# tic_tac_toe_wire.net
KiCad netlist of a schematic drawn in EAGLE
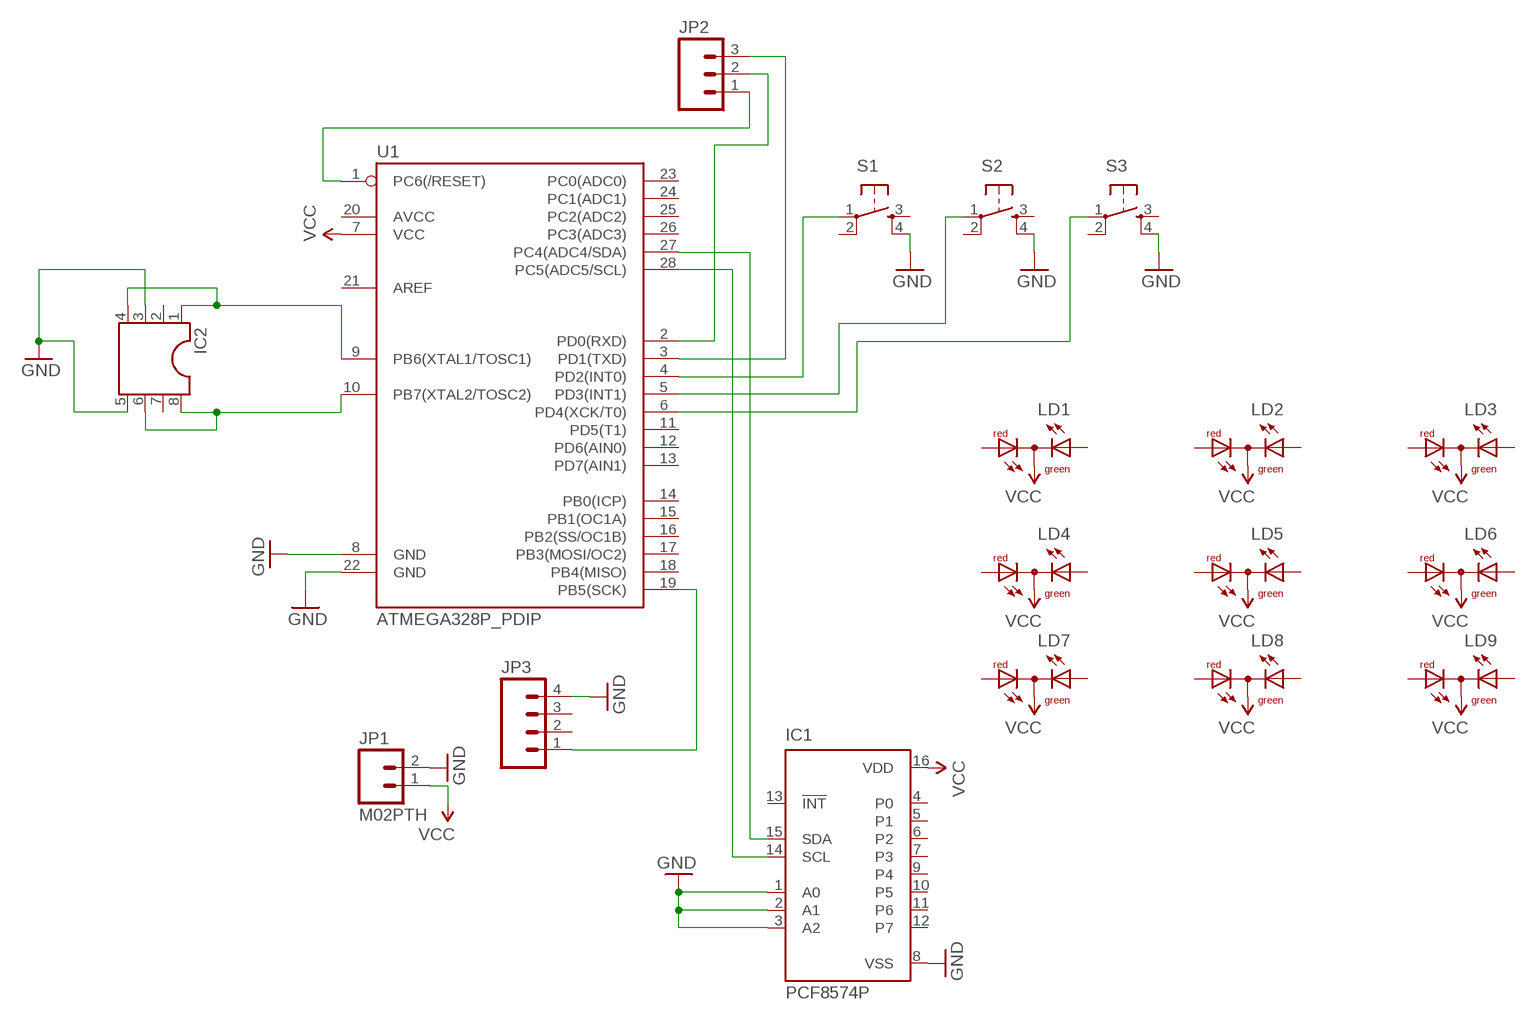
[diagram p0: schematic, sheet 1]

(export (version "E")
  (design (tool "Eeschema 10.0.6"))
  (components
    (comp (ref "IC1")
      (value "PCF8574P")
      (footprint "eagle-import:DIL16")
      (fields (field (name "MPN") "PCF8574PN"))
      (libsource (lib "eagle-import") (part "PCF8574P"))
    )
    (comp (ref "IC2")
      (value "DIL8S")
      (footprint "eagle-import:SOCKET-08")
      (libsource (lib "eagle-import") (part "DIL8S"))
    )
    (comp (ref "JP1")
      (value "M02PTH")
      (footprint "eagle-import:1X02")
      (libsource (lib "eagle-import") (part "M02PTH"))
    )
    (comp (ref "JP2")
      (value "M03PTH")
      (footprint "eagle-import:1X03")
      (libsource (lib "eagle-import") (part "M03PTH"))
    )
    (comp (ref "JP3")
      (value "M04PTH")
      (footprint "eagle-import:1X04")
      (libsource (lib "eagle-import") (part "M04PTH"))
    )
    (comp (ref "LD1")
      (value "DUOLED-RG-C")
      (footprint "eagle-import:DUOLED-C-5MM")
      (libsource (lib "eagle-import") (part "DUOLED-RG-C"))
    )
    (comp (ref "LD2")
      (value "DUOLED-RG-C")
      (footprint "eagle-import:DUOLED-C-5MM")
      (libsource (lib "eagle-import") (part "DUOLED-RG-C"))
    )
    (comp (ref "LD3")
      (value "DUOLED-RG-C")
      (footprint "eagle-import:DUOLED-C-5MM")
      (libsource (lib "eagle-import") (part "DUOLED-RG-C"))
    )
    (comp (ref "LD4")
      (value "DUOLED-RG-C")
      (footprint "eagle-import:DUOLED-C-5MM")
      (libsource (lib "eagle-import") (part "DUOLED-RG-C"))
    )
    (comp (ref "LD5")
      (value "DUOLED-RG-C")
      (footprint "eagle-import:DUOLED-C-5MM")
      (libsource (lib "eagle-import") (part "DUOLED-RG-C"))
    )
    (comp (ref "LD6")
      (value "DUOLED-RG-C")
      (footprint "eagle-import:DUOLED-C-5MM")
      (libsource (lib "eagle-import") (part "DUOLED-RG-C"))
    )
    (comp (ref "LD7")
      (value "DUOLED-RG-C")
      (footprint "eagle-import:DUOLED-C-5MM")
      (libsource (lib "eagle-import") (part "DUOLED-RG-C"))
    )
    (comp (ref "LD8")
      (value "DUOLED-RG-C")
      (footprint "eagle-import:DUOLED-C-5MM")
      (libsource (lib "eagle-import") (part "DUOLED-RG-C"))
    )
    (comp (ref "LD9")
      (value "DUOLED-RG-C")
      (footprint "eagle-import:DUOLED-C-5MM")
      (libsource (lib "eagle-import") (part "DUOLED-RG-C"))
    )
    (comp (ref "S1")
      (value "TAC_SWITCHPTH")
      (footprint "eagle-import:TACTILE-PTH")
      (libsource (lib "eagle-import") (part "TAC_SWITCHPTH"))
    )
    (comp (ref "S2")
      (value "TAC_SWITCHPTH")
      (footprint "eagle-import:TACTILE-PTH")
      (libsource (lib "eagle-import") (part "TAC_SWITCHPTH"))
    )
    (comp (ref "S3")
      (value "TAC_SWITCHPTH")
      (footprint "eagle-import:TACTILE-PTH")
      (libsource (lib "eagle-import") (part "TAC_SWITCHPTH"))
    )
    (comp (ref "U1")
      (value "ATMEGA328P_PDIP")
      (footprint "eagle-import:DIL28-3")
      (libsource (lib "eagle-import") (part "ATMEGA328P_PDIP"))
    )
  )
  (nets
    (net (code "1") (name "GND") (class "Default")
      (node (ref "IC1") (pin "1") (pinfunction "A0_1") (pintype "input"))
      (node (ref "IC1") (pin "2") (pinfunction "A1_2") (pintype "input"))
      (node (ref "IC1") (pin "3") (pinfunction "A2_3") (pintype "input"))
      (node (ref "IC1") (pin "8") (pinfunction "VSS_8") (pintype "power_in"))
      (node (ref "IC2") (pin "3") (pinfunction "3_3") (pintype "passive"))
      (node (ref "IC2") (pin "5") (pinfunction "5_5") (pintype "passive"))
      (node (ref "JP1") (pin "2") (pinfunction "2_2") (pintype "passive"))
      (node (ref "JP3") (pin "4") (pinfunction "4_4") (pintype "passive"))
      (node (ref "S1") (pin "4") (pinfunction "4_4") (pintype "passive"))
      (node (ref "S2") (pin "4") (pinfunction "4_4") (pintype "passive"))
      (node (ref "S3") (pin "4") (pinfunction "4_4") (pintype "passive"))
      (node (ref "U1") (pin "22") (pinfunction "GND_22") (pintype "bidirectional"))
      (node (ref "U1") (pin "8") (pinfunction "GND_8") (pintype "bidirectional"))
    )
    (net (code "2") (name "Net-(IC1-SCL)") (class "Default")
      (node (ref "IC1") (pin "14") (pinfunction "SCL_14") (pintype "input"))
      (node (ref "U1") (pin "28") (pinfunction "PC5(ADC5/SCL)_28") (pintype "bidirectional"))
    )
    (net (code "3") (name "Net-(IC1-SDA)") (class "Default")
      (node (ref "IC1") (pin "15") (pinfunction "SDA_15") (pintype "bidirectional"))
      (node (ref "U1") (pin "27") (pinfunction "PC4(ADC4/SDA)_27") (pintype "bidirectional"))
    )
    (net (code "4") (name "Net-(U1-PB5(SCK))") (class "Default")
      (node (ref "JP3") (pin "1") (pinfunction "1_1") (pintype "passive"))
      (node (ref "U1") (pin "19") (pinfunction "PB5(SCK)_19") (pintype "bidirectional"))
    )
    (net (code "5") (name "Net-(U1-PB6(XTAL1{slash}TOSC1))") (class "Default")
      (node (ref "IC2") (pin "1") (pinfunction "1_1") (pintype "passive"))
      (node (ref "IC2") (pin "4") (pinfunction "4_4") (pintype "passive"))
      (node (ref "U1") (pin "9") (pinfunction "PB6(XTAL1/TOSC1)_9") (pintype "bidirectional"))
    )
    (net (code "6") (name "Net-(U1-PB7(XTAL2{slash}TOSC2))") (class "Default")
      (node (ref "IC2") (pin "6") (pinfunction "6_6") (pintype "passive"))
      (node (ref "IC2") (pin "8") (pinfunction "8_8") (pintype "passive"))
      (node (ref "U1") (pin "10") (pinfunction "PB7(XTAL2/TOSC2)_10") (pintype "bidirectional"))
    )
    (net (code "7") (name "Net-(U1-PC6({slash}RESET))") (class "Default")
      (node (ref "JP2") (pin "1") (pinfunction "1_1") (pintype "passive"))
      (node (ref "U1") (pin "1") (pinfunction "PC6(/RESET)_1") (pintype "bidirectional"))
    )
    (net (code "8") (name "Net-(U1-PD0(RXD))") (class "Default")
      (node (ref "JP2") (pin "2") (pinfunction "2_2") (pintype "passive"))
      (node (ref "U1") (pin "2") (pinfunction "PD0(RXD)_2") (pintype "bidirectional"))
    )
    (net (code "9") (name "Net-(U1-PD1(TXD))") (class "Default")
      (node (ref "JP2") (pin "3") (pinfunction "3_3") (pintype "passive"))
      (node (ref "U1") (pin "3") (pinfunction "PD1(TXD)_3") (pintype "bidirectional"))
    )
    (net (code "10") (name "Net-(U1-PD2(INT0))") (class "Default")
      (node (ref "S1") (pin "1") (pinfunction "1_1") (pintype "passive"))
      (node (ref "U1") (pin "4") (pinfunction "PD2(INT0)_4") (pintype "bidirectional"))
    )
    (net (code "11") (name "Net-(U1-PD3(INT1))") (class "Default")
      (node (ref "S2") (pin "1") (pinfunction "1_1") (pintype "passive"))
      (node (ref "U1") (pin "5") (pinfunction "PD3(INT1)_5") (pintype "bidirectional"))
    )
    (net (code "12") (name "Net-(U1-PD4(XCK{slash}T0))") (class "Default")
      (node (ref "S3") (pin "1") (pinfunction "1_1") (pintype "passive"))
      (node (ref "U1") (pin "6") (pinfunction "PD4(XCK/T0)_6") (pintype "bidirectional"))
    )
    (net (code "13") (name "VCC") (class "Default")
      (node (ref "IC1") (pin "16") (pinfunction "VDD_16") (pintype "power_in"))
      (node (ref "JP1") (pin "1") (pinfunction "1_1") (pintype "passive"))
      (node (ref "LD1") (pin "C") (pinfunction "C_C") (pintype "passive"))
      (node (ref "LD2") (pin "C") (pinfunction "C_C") (pintype "passive"))
      (node (ref "LD3") (pin "C") (pinfunction "C_C") (pintype "passive"))
      (node (ref "LD4") (pin "C") (pinfunction "C_C") (pintype "passive"))
      (node (ref "LD5") (pin "C") (pinfunction "C_C") (pintype "passive"))
      (node (ref "LD6") (pin "C") (pinfunction "C_C") (pintype "passive"))
      (node (ref "LD7") (pin "C") (pinfunction "C_C") (pintype "passive"))
      (node (ref "LD8") (pin "C") (pinfunction "C_C") (pintype "passive"))
      (node (ref "LD9") (pin "C") (pinfunction "C_C") (pintype "passive"))
      (node (ref "U1") (pin "7") (pinfunction "VCC_7") (pintype "bidirectional"))
    )
    (net (code "14") (name "unconnected-(IC1-P0-Pad4)") (class "Default")
      (node (ref "IC1") (pin "4") (pinfunction "P0_4") (pintype "bidirectional"))
    )
    (net (code "15") (name "unconnected-(IC1-P1-Pad5)") (class "Default")
      (node (ref "IC1") (pin "5") (pinfunction "P1_5") (pintype "bidirectional"))
    )
    (net (code "16") (name "unconnected-(IC1-P2-Pad6)") (class "Default")
      (node (ref "IC1") (pin "6") (pinfunction "P2_6") (pintype "bidirectional"))
    )
    (net (code "17") (name "unconnected-(IC1-P3-Pad7)") (class "Default")
      (node (ref "IC1") (pin "7") (pinfunction "P3_7") (pintype "bidirectional"))
    )
    (net (code "18") (name "unconnected-(IC1-P4-Pad9)") (class "Default")
      (node (ref "IC1") (pin "9") (pinfunction "P4_9") (pintype "bidirectional"))
    )
    (net (code "19") (name "unconnected-(IC1-P5-Pad10)") (class "Default")
      (node (ref "IC1") (pin "10") (pinfunction "P5_10") (pintype "bidirectional"))
    )
    (net (code "20") (name "unconnected-(IC1-P6-Pad11)") (class "Default")
      (node (ref "IC1") (pin "11") (pinfunction "P6_11") (pintype "bidirectional"))
    )
    (net (code "21") (name "unconnected-(IC1-P7-Pad12)") (class "Default")
      (node (ref "IC1") (pin "12") (pinfunction "P7_12") (pintype "bidirectional"))
    )
    (net (code "22") (name "unconnected-(IC1-~{INT}-Pad13)") (class "Default")
      (node (ref "IC1") (pin "13") (pinfunction "~{INT}_13") (pintype "output"))
    )
    (net (code "23") (name "unconnected-(IC2-Pad2)") (class "Default")
      (node (ref "IC2") (pin "2") (pinfunction "2_2") (pintype "passive"))
    )
    (net (code "24") (name "unconnected-(IC2-Pad7)") (class "Default")
      (node (ref "IC2") (pin "7") (pinfunction "7_7") (pintype "passive"))
    )
    (net (code "25") (name "unconnected-(JP3-Pad2)") (class "Default")
      (node (ref "JP3") (pin "2") (pinfunction "2_2") (pintype "passive"))
    )
    (net (code "26") (name "unconnected-(JP3-Pad3)") (class "Default")
      (node (ref "JP3") (pin "3") (pinfunction "3_3") (pintype "passive"))
    )
    (net (code "27") (name "unconnected-(LD1-AG-PadAX)") (class "Default")
      (node (ref "LD1") (pin "AX") (pinfunction "AG_AX") (pintype "passive"))
    )
    (net (code "28") (name "unconnected-(LD1-PadAR)") (class "Default")
      (node (ref "LD1") (pin "AR") (pinfunction "AR_AR") (pintype "passive"))
    )
    (net (code "29") (name "unconnected-(LD2-AG-PadAX)") (class "Default")
      (node (ref "LD2") (pin "AX") (pinfunction "AG_AX") (pintype "passive"))
    )
    (net (code "30") (name "unconnected-(LD2-PadAR)") (class "Default")
      (node (ref "LD2") (pin "AR") (pinfunction "AR_AR") (pintype "passive"))
    )
    (net (code "31") (name "unconnected-(LD3-AG-PadAX)") (class "Default")
      (node (ref "LD3") (pin "AX") (pinfunction "AG_AX") (pintype "passive"))
    )
    (net (code "32") (name "unconnected-(LD3-PadAR)") (class "Default")
      (node (ref "LD3") (pin "AR") (pinfunction "AR_AR") (pintype "passive"))
    )
    (net (code "33") (name "unconnected-(LD4-AG-PadAX)") (class "Default")
      (node (ref "LD4") (pin "AX") (pinfunction "AG_AX") (pintype "passive"))
    )
    (net (code "34") (name "unconnected-(LD4-PadAR)") (class "Default")
      (node (ref "LD4") (pin "AR") (pinfunction "AR_AR") (pintype "passive"))
    )
    (net (code "35") (name "unconnected-(LD5-AG-PadAX)") (class "Default")
      (node (ref "LD5") (pin "AX") (pinfunction "AG_AX") (pintype "passive"))
    )
    (net (code "36") (name "unconnected-(LD5-PadAR)") (class "Default")
      (node (ref "LD5") (pin "AR") (pinfunction "AR_AR") (pintype "passive"))
    )
    (net (code "37") (name "unconnected-(LD6-AG-PadAX)") (class "Default")
      (node (ref "LD6") (pin "AX") (pinfunction "AG_AX") (pintype "passive"))
    )
    (net (code "38") (name "unconnected-(LD6-PadAR)") (class "Default")
      (node (ref "LD6") (pin "AR") (pinfunction "AR_AR") (pintype "passive"))
    )
    (net (code "39") (name "unconnected-(LD7-AG-PadAX)") (class "Default")
      (node (ref "LD7") (pin "AX") (pinfunction "AG_AX") (pintype "passive"))
    )
    (net (code "40") (name "unconnected-(LD7-PadAR)") (class "Default")
      (node (ref "LD7") (pin "AR") (pinfunction "AR_AR") (pintype "passive"))
    )
    (net (code "41") (name "unconnected-(LD8-AG-PadAX)") (class "Default")
      (node (ref "LD8") (pin "AX") (pinfunction "AG_AX") (pintype "passive"))
    )
    (net (code "42") (name "unconnected-(LD8-PadAR)") (class "Default")
      (node (ref "LD8") (pin "AR") (pinfunction "AR_AR") (pintype "passive"))
    )
    (net (code "43") (name "unconnected-(LD9-AG-PadAX)") (class "Default")
      (node (ref "LD9") (pin "AX") (pinfunction "AG_AX") (pintype "passive"))
    )
    (net (code "44") (name "unconnected-(LD9-PadAR)") (class "Default")
      (node (ref "LD9") (pin "AR") (pinfunction "AR_AR") (pintype "passive"))
    )
    (net (code "45") (name "unconnected-(S1-Pad2)") (class "Default")
      (node (ref "S1") (pin "2") (pinfunction "2_2") (pintype "passive"))
    )
    (net (code "46") (name "unconnected-(S1-Pad3)") (class "Default")
      (node (ref "S1") (pin "3") (pinfunction "3_3") (pintype "passive"))
    )
    (net (code "47") (name "unconnected-(S2-Pad2)") (class "Default")
      (node (ref "S2") (pin "2") (pinfunction "2_2") (pintype "passive"))
    )
    (net (code "48") (name "unconnected-(S2-Pad3)") (class "Default")
      (node (ref "S2") (pin "3") (pinfunction "3_3") (pintype "passive"))
    )
    (net (code "49") (name "unconnected-(S3-Pad2)") (class "Default")
      (node (ref "S3") (pin "2") (pinfunction "2_2") (pintype "passive"))
    )
    (net (code "50") (name "unconnected-(S3-Pad3)") (class "Default")
      (node (ref "S3") (pin "3") (pinfunction "3_3") (pintype "passive"))
    )
    (net (code "51") (name "unconnected-(U1-AREF-Pad21)") (class "Default")
      (node (ref "U1") (pin "21") (pinfunction "AREF_21") (pintype "bidirectional"))
    )
    (net (code "52") (name "unconnected-(U1-AVCC-Pad20)") (class "Default")
      (node (ref "U1") (pin "20") (pinfunction "AVCC_20") (pintype "bidirectional"))
    )
    (net (code "53") (name "unconnected-(U1-PB0(ICP)-Pad14)") (class "Default")
      (node (ref "U1") (pin "14") (pinfunction "PB0(ICP)_14") (pintype "bidirectional"))
    )
    (net (code "54") (name "unconnected-(U1-PB1(OC1A)-Pad15)") (class "Default")
      (node (ref "U1") (pin "15") (pinfunction "PB1(OC1A)_15") (pintype "bidirectional"))
    )
    (net (code "55") (name "unconnected-(U1-PB2(SS{slash}OC1B)-Pad16)") (class "Default")
      (node (ref "U1") (pin "16") (pinfunction "PB2(SS/OC1B)_16") (pintype "bidirectional"))
    )
    (net (code "56") (name "unconnected-(U1-PB3(MOSI{slash}OC2)-Pad17)") (class "Default")
      (node (ref "U1") (pin "17") (pinfunction "PB3(MOSI/OC2)_17") (pintype "bidirectional"))
    )
    (net (code "57") (name "unconnected-(U1-PB4(MISO)-Pad18)") (class "Default")
      (node (ref "U1") (pin "18") (pinfunction "PB4(MISO)_18") (pintype "bidirectional"))
    )
    (net (code "58") (name "unconnected-(U1-PC0(ADC0)-Pad23)") (class "Default")
      (node (ref "U1") (pin "23") (pinfunction "PC0(ADC0)_23") (pintype "bidirectional"))
    )
    (net (code "59") (name "unconnected-(U1-PC1(ADC1)-Pad24)") (class "Default")
      (node (ref "U1") (pin "24") (pinfunction "PC1(ADC1)_24") (pintype "bidirectional"))
    )
    (net (code "60") (name "unconnected-(U1-PC2(ADC2)-Pad25)") (class "Default")
      (node (ref "U1") (pin "25") (pinfunction "PC2(ADC2)_25") (pintype "bidirectional"))
    )
    (net (code "61") (name "unconnected-(U1-PC3(ADC3)-Pad26)") (class "Default")
      (node (ref "U1") (pin "26") (pinfunction "PC3(ADC3)_26") (pintype "bidirectional"))
    )
    (net (code "62") (name "unconnected-(U1-PD5(T1)-Pad11)") (class "Default")
      (node (ref "U1") (pin "11") (pinfunction "PD5(T1)_11") (pintype "bidirectional"))
    )
    (net (code "63") (name "unconnected-(U1-PD6(AIN0)-Pad12)") (class "Default")
      (node (ref "U1") (pin "12") (pinfunction "PD6(AIN0)_12") (pintype "bidirectional"))
    )
    (net (code "64") (name "unconnected-(U1-PD7(AIN1)-Pad13)") (class "Default")
      (node (ref "U1") (pin "13") (pinfunction "PD7(AIN1)_13") (pintype "bidirectional"))
    )
  )
)
